# Joystick.net
KiCad netlist of a schematic drawn in Altium Designer
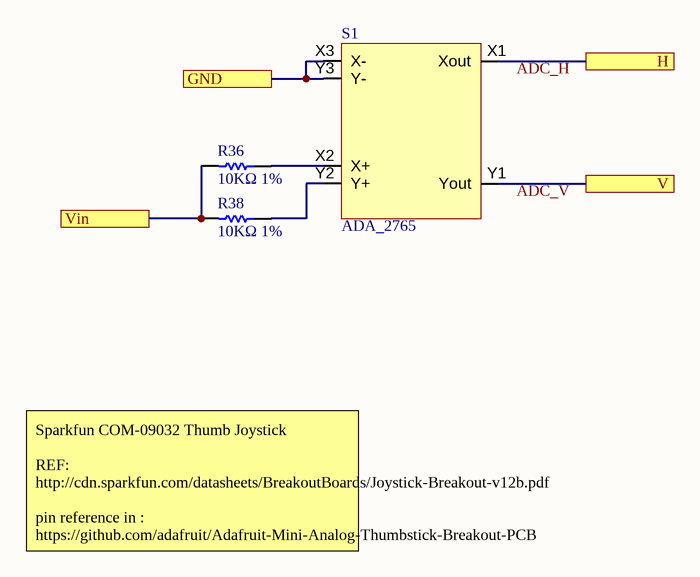
[diagram p0: Joystick.SchDoc]

(export (version "E")
  (design (tool "Eeschema 10.0.6"))
  (components
    (comp (ref "R36")
      (value "10KΩ 1%")
      (footprint "RESC0603(1608)_N")
      (description "10K 0.1W 1% 0603 (1608 Metric)  SMD")
      (fields (field (name "POWER") "0.1 W") (field (name "TOLERANCE") "1 %"))
      (libsource (lib "Altium Content Vault") (part "RES"))
    )
    (comp (ref "R38")
      (value "10KΩ 1%")
      (footprint "RESC0603(1608)_N")
      (description "10K 0.1W 1% 0603 (1608 Metric)  SMD")
      (fields (field (name "POWER") "0.1 W") (field (name "TOLERANCE") "1 %"))
      (libsource (lib "Altium Content Vault") (part "RES"))
    )
    (comp (ref "S1")
      (value "ADA_2765")
      (footprint "ADA_2765")
      (description "Mini 2-Axis Analog Thumbstick")
      (fields
        (field (name "MANUFACTURER") "Adafruit Industries")
        (field (name "MANUFACTURER PART NUMBER") "2765")
      )
      (libsource (lib "Schematics") (part "ADA_2765"))
    )
  )
  (nets
    (net (code "3") (name "/GND") (class "Default")
      (node (ref "S1") (pin "X3") (pinfunction "X-_X3") (pintype "passive"))
      (node (ref "S1") (pin "Y3") (pinfunction "Y-_Y3") (pintype "passive"))
    )
    (net (code "4") (name "/H") (class "Default")
      (node (ref "S1") (pin "X1") (pinfunction "Xout_X1") (pintype "passive"))
    )
    (net (code "5") (name "/V") (class "Default")
      (node (ref "S1") (pin "Y1") (pinfunction "Yout_Y1") (pintype "passive"))
    )
    (net (code "6") (name "/Vin") (class "Default")
      (node (ref "R36") (pin "2") (pinfunction "2_2") (pintype "passive"))
      (node (ref "R38") (pin "2") (pinfunction "2_2") (pintype "passive"))
    )
    (net (code "7") (name "Net-(S1-X+)") (class "Default")
      (node (ref "R36") (pin "1") (pinfunction "1_1") (pintype "passive"))
      (node (ref "S1") (pin "X2") (pinfunction "X+_X2") (pintype "passive"))
    )
    (net (code "8") (name "Net-(S1-Y+)") (class "Default")
      (node (ref "R38") (pin "1") (pinfunction "1_1") (pintype "passive"))
      (node (ref "S1") (pin "Y2") (pinfunction "Y+_Y2") (pintype "passive"))
    )
  )
)
